# 05_UART_Interface.net
KiCad netlist of a schematic drawn in Altium Designer
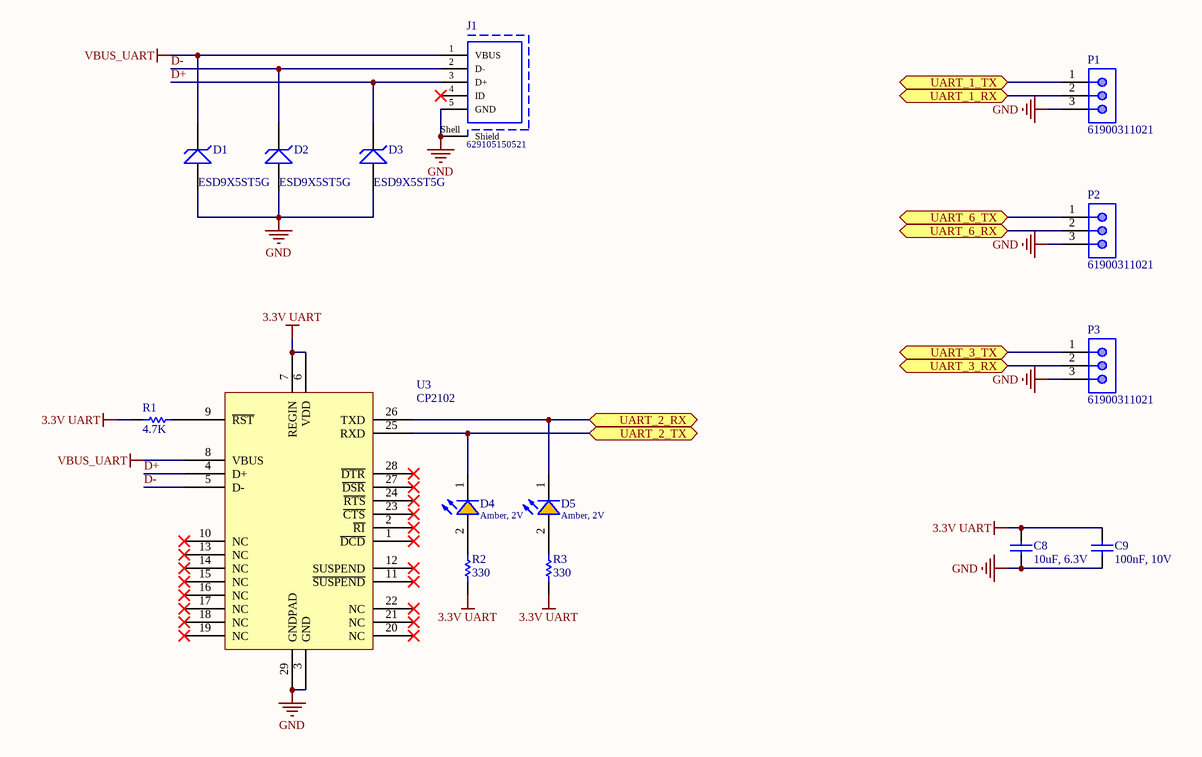
[diagram p0: 05_UART_Interface.SchDoc]

(export (version "E")
  (design (tool "Eeschema 10.0.6"))
  (components
    (comp (ref "C8")
      (value "10uF, 6.3V")
      (footprint "WCAP-CSGP_0603_H=0.8mm_Reflow")
      (description "WCAP-CSGP Multilayer Ceramic Chip Capacitor, General Purpose, size 0603, X5R, 10uF, 6.3V")
      (fields
        (field (name "MANUFACTURER PART NUMBER") "885012106006")
        (field (name "MANUFACTURER") "Wurth Elektronik")
      )
      (libsource (lib "Altium_WCAP-CSGP (rev20a)") (part "885012106006"))
    )
    (comp (ref "C9")
      (value "100nF, 10V")
      (footprint "WCAP-CSGP_0603_H=0.8mm_Reflow")
      (description "WCAP-CSGP Multilayer Ceramic Chip Capacitor, General Purpose, size 0603, X7R, 100nF, 10V")
      (fields
        (field (name "MANUFACTURER PART NUMBER") "885012206020")
        (field (name "MANUFACTURER") "Wurth Elektronik")
      )
      (libsource (lib "Altium_WCAP-CSGP (rev20a)") (part "885012206020"))
    )
    (comp (ref "D1")
      (value "ESD9X5ST5G")
      (footprint "SODFL100X40-2N")
      (fields (field (name "MANUFACTURER") "ON Semiconductor"))
      (libsource (lib "MiclsLib") (part "ESD9X5ST5G"))
    )
    (comp (ref "D2")
      (value "ESD9X5ST5G")
      (footprint "SODFL100X40-2N")
      (fields (field (name "MANUFACTURER") "ON Semiconductor"))
      (libsource (lib "MiclsLib") (part "ESD9X5ST5G"))
    )
    (comp (ref "D3")
      (value "ESD9X5ST5G")
      (footprint "SODFL100X40-2N")
      (fields (field (name "MANUFACTURER") "ON Semiconductor"))
      (libsource (lib "MiclsLib") (part "ESD9X5ST5G"))
    )
    (comp (ref "D4")
      (value "Amber, 2V")
      (footprint "WL-SMCW_0603_H=0.7mm")
      (description "WL-SMCW SMT Mono-color Chip LED Waterclear, size 0603, Amber, 2V, 140deg")
      (fields (field (name "PART NUMBER") "150060AS75000") (field (name "PUBLISHER") "Wurth Elektronik"))
      (libsource (lib "Altium_WL-SMCW (rev20a)") (part "150060AS75000"))
    )
    (comp (ref "D5")
      (value "Amber, 2V")
      (footprint "WL-SMCW_0603_H=0.7mm")
      (description "WL-SMCW SMT Mono-color Chip LED Waterclear, size 0603, Amber, 2V, 140deg")
      (fields (field (name "PART NUMBER") "150060AS75000") (field (name "PUBLISHER") "Wurth Elektronik"))
      (libsource (lib "Altium_WL-SMCW (rev20a)") (part "150060AS75000"))
    )
    (comp (ref "J1")
      (value "629105150521")
      (footprint "629105150521")
      (description "Micro USB 2.0 Type B Receptacle WR-COM, Horizontal, SMT, with Pegs, High Current at Pin 1 & Pin 5")
      (fields (field (name "PUBLISHER") "Wurth Elektronik"))
      (libsource (lib "ALTIUM-WR-COM_USB_20-rev18d") (part "629105150521"))
    )
    (comp (ref "P1")
      (value "61900311021")
      (footprint "61900311021")
      (description "WR-WTB THT Male Left Angled Bottom Locking Header, pitch 2.54mm, 3p")
      (fields (field (name "PUBLISHER") "Wurth Elektronik"))
      (libsource (lib "653008114822_Altium_WR-WTB_rev20a") (part "61900311021"))
    )
    (comp (ref "P2")
      (value "61900311021")
      (footprint "61900311021")
      (description "WR-WTB THT Male Left Angled Bottom Locking Header, pitch 2.54mm, 3p")
      (fields (field (name "PUBLISHER") "Wurth Elektronik"))
      (libsource (lib "653008114822_Altium_WR-WTB_rev20a") (part "61900311021"))
    )
    (comp (ref "P3")
      (value "61900311021")
      (footprint "61900311021")
      (description "WR-WTB THT Male Left Angled Bottom Locking Header, pitch 2.54mm, 3p")
      (fields (field (name "PUBLISHER") "Wurth Elektronik"))
      (libsource (lib "653008114822_Altium_WR-WTB_rev20a") (part "61900311021"))
    )
    (comp (ref "R1")
      (value "4.7K")
      (footprint "RES-SM-0603")
      (description "Resistor")
      (fields (field (name "Comment") "RESISTOR SMD"))
      (libsource (lib "PIF_Library") (part "RESISTOR SMD"))
    )
    (comp (ref "R2")
      (value "330")
      (footprint "RES-SM-0603")
      (description "Resistor")
      (fields (field (name "Comment") "RESISTOR SMD"))
      (libsource (lib "PIF_Library") (part "RESISTOR SMD"))
    )
    (comp (ref "R3")
      (value "330")
      (footprint "RES-SM-0603")
      (description "Resistor")
      (fields (field (name "Comment") "RESISTOR SMD"))
      (libsource (lib "PIF_Library") (part "RESISTOR SMD"))
    )
    (comp (ref "U3")
      (value "CP2102")
      (footprint "QFN50P500X500X90_HS-29N")
      (libsource (lib "MiclsLib") (part "CP2102"))
    )
  )
  (nets
    (net (code "1") (name "/D+") (class "Default")
      (node (ref "D3") (pin "1") (pinfunction "1_1") (pintype "passive"))
      (node (ref "J1") (pin "3") (pinfunction "D+_3") (pintype "passive"))
      (node (ref "U3") (pin "4") (pinfunction "D+_4") (pintype "passive"))
    )
    (net (code "2") (name "/D-") (class "Default")
      (node (ref "D2") (pin "1") (pinfunction "1_1") (pintype "passive"))
      (node (ref "J1") (pin "2") (pinfunction "D-_2") (pintype "passive"))
      (node (ref "U3") (pin "5") (pinfunction "D-_5") (pintype "passive"))
    )
    (net (code "3") (name "/UART_1_RX") (class "Default")
      (node (ref "P1") (pin "2") (pinfunction "2_2") (pintype "passive"))
    )
    (net (code "4") (name "/UART_1_TX") (class "Default")
      (node (ref "P1") (pin "1") (pinfunction "1_1") (pintype "passive"))
    )
    (net (code "5") (name "/UART_2_RX") (class "Default")
      (node (ref "D5") (pin "1") (pinfunction "K_1") (pintype "passive"))
      (node (ref "U3") (pin "26") (pinfunction "TXD_26") (pintype "passive"))
    )
    (net (code "6") (name "/UART_2_TX") (class "Default")
      (node (ref "D4") (pin "1") (pinfunction "K_1") (pintype "passive"))
      (node (ref "U3") (pin "25") (pinfunction "RXD_25") (pintype "passive"))
    )
    (net (code "7") (name "/UART_3_RX") (class "Default")
      (node (ref "P3") (pin "2") (pinfunction "2_2") (pintype "passive"))
    )
    (net (code "8") (name "/UART_3_TX") (class "Default")
      (node (ref "P3") (pin "1") (pinfunction "1_1") (pintype "passive"))
    )
    (net (code "9") (name "/UART_6_RX") (class "Default")
      (node (ref "P2") (pin "2") (pinfunction "2_2") (pintype "passive"))
    )
    (net (code "10") (name "/UART_6_TX") (class "Default")
      (node (ref "P2") (pin "1") (pinfunction "1_1") (pintype "passive"))
    )
    (net (code "11") (name "3.3V UART") (class "Default")
      (node (ref "C8") (pin "2") (pinfunction "2_2") (pintype "passive"))
      (node (ref "C9") (pin "2") (pinfunction "2_2") (pintype "passive"))
      (node (ref "R1") (pin "2") (pinfunction "2_2") (pintype "passive"))
      (node (ref "R2") (pin "2") (pinfunction "2_2") (pintype "passive"))
      (node (ref "R3") (pin "2") (pinfunction "2_2") (pintype "passive"))
      (node (ref "U3") (pin "6") (pinfunction "VDD_6") (pintype "passive"))
      (node (ref "U3") (pin "7") (pinfunction "REGIN_7") (pintype "passive"))
    )
    (net (code "12") (name "GND") (class "Default")
      (node (ref "C8") (pin "1") (pinfunction "1_1") (pintype "passive"))
      (node (ref "C9") (pin "1") (pinfunction "1_1") (pintype "passive"))
      (node (ref "D1") (pin "2") (pinfunction "2_2") (pintype "passive"))
      (node (ref "D2") (pin "2") (pinfunction "2_2") (pintype "passive"))
      (node (ref "D3") (pin "2") (pinfunction "2_2") (pintype "passive"))
      (node (ref "J1") (pin "5") (pinfunction "GND_5") (pintype "passive"))
      (node (ref "J1") (pin "Shell") (pinfunction "Shield_Shell") (pintype "passive"))
      (node (ref "P1") (pin "3") (pinfunction "3_3") (pintype "passive"))
      (node (ref "P2") (pin "3") (pinfunction "3_3") (pintype "passive"))
      (node (ref "P3") (pin "3") (pinfunction "3_3") (pintype "passive"))
      (node (ref "U3") (pin "29") (pinfunction "GNDPAD_29") (pintype "passive"))
      (node (ref "U3") (pin "3") (pinfunction "GND_3") (pintype "passive"))
    )
    (net (code "13") (name "Net-(D4-A)") (class "Default")
      (node (ref "D4") (pin "2") (pinfunction "A_2") (pintype "passive"))
      (node (ref "R2") (pin "1") (pinfunction "1_1") (pintype "passive"))
    )
    (net (code "14") (name "Net-(D5-A)") (class "Default")
      (node (ref "D5") (pin "2") (pinfunction "A_2") (pintype "passive"))
      (node (ref "R3") (pin "1") (pinfunction "1_1") (pintype "passive"))
    )
    (net (code "15") (name "Net-(U3-~{RST})") (class "Default")
      (node (ref "R1") (pin "1") (pinfunction "1_1") (pintype "passive"))
      (node (ref "U3") (pin "9") (pinfunction "~{RST}_9") (pintype "passive"))
    )
    (net (code "16") (name "VBUS_UART") (class "Default")
      (node (ref "D1") (pin "1") (pinfunction "1_1") (pintype "passive"))
      (node (ref "J1") (pin "1") (pinfunction "VBUS_1") (pintype "passive"))
      (node (ref "U3") (pin "8") (pinfunction "VBUS_8") (pintype "passive"))
    )
    (net (code "17") (name "unconnected-(J1-ID-Pad4)") (class "Default")
      (node (ref "J1") (pin "4") (pinfunction "ID_4") (pintype "passive+no_connect"))
    )
    (net (code "18") (name "unconnected-(U3-NC-Pad10)") (class "Default")
      (node (ref "U3") (pin "10") (pinfunction "NC_10") (pintype "passive+no_connect"))
    )
    (net (code "19") (name "unconnected-(U3-NC-Pad13)") (class "Default")
      (node (ref "U3") (pin "13") (pinfunction "NC_13") (pintype "passive+no_connect"))
    )
    (net (code "20") (name "unconnected-(U3-NC-Pad14)") (class "Default")
      (node (ref "U3") (pin "14") (pinfunction "NC_14") (pintype "passive+no_connect"))
    )
    (net (code "21") (name "unconnected-(U3-NC-Pad15)") (class "Default")
      (node (ref "U3") (pin "15") (pinfunction "NC_15") (pintype "passive+no_connect"))
    )
    (net (code "22") (name "unconnected-(U3-NC-Pad16)") (class "Default")
      (node (ref "U3") (pin "16") (pinfunction "NC_16") (pintype "passive+no_connect"))
    )
    (net (code "23") (name "unconnected-(U3-NC-Pad17)") (class "Default")
      (node (ref "U3") (pin "17") (pinfunction "NC_17") (pintype "passive+no_connect"))
    )
    (net (code "24") (name "unconnected-(U3-NC-Pad18)") (class "Default")
      (node (ref "U3") (pin "18") (pinfunction "NC_18") (pintype "passive+no_connect"))
    )
    (net (code "25") (name "unconnected-(U3-NC-Pad19)") (class "Default")
      (node (ref "U3") (pin "19") (pinfunction "NC_19") (pintype "passive+no_connect"))
    )
    (net (code "26") (name "unconnected-(U3-NC-Pad20)") (class "Default")
      (node (ref "U3") (pin "20") (pinfunction "NC_20") (pintype "passive+no_connect"))
    )
    (net (code "27") (name "unconnected-(U3-NC-Pad21)") (class "Default")
      (node (ref "U3") (pin "21") (pinfunction "NC_21") (pintype "passive+no_connect"))
    )
    (net (code "28") (name "unconnected-(U3-NC-Pad22)") (class "Default")
      (node (ref "U3") (pin "22") (pinfunction "NC_22") (pintype "passive+no_connect"))
    )
    (net (code "29") (name "unconnected-(U3-SUSPEND-Pad12)") (class "Default")
      (node (ref "U3") (pin "12") (pinfunction "SUSPEND_12") (pintype "passive+no_connect"))
    )
    (net (code "30") (name "unconnected-(U3-~{CTS}-Pad23)") (class "Default")
      (node (ref "U3") (pin "23") (pinfunction "~{CTS}_23") (pintype "passive+no_connect"))
    )
    (net (code "31") (name "unconnected-(U3-~{DCD}-Pad1)") (class "Default")
      (node (ref "U3") (pin "1") (pinfunction "~{DCD}_1") (pintype "passive+no_connect"))
    )
    (net (code "32") (name "unconnected-(U3-~{DSR}-Pad27)") (class "Default")
      (node (ref "U3") (pin "27") (pinfunction "~{DSR}_27") (pintype "passive+no_connect"))
    )
    (net (code "33") (name "unconnected-(U3-~{DTR}-Pad28)") (class "Default")
      (node (ref "U3") (pin "28") (pinfunction "~{DTR}_28") (pintype "passive+no_connect"))
    )
    (net (code "34") (name "unconnected-(U3-~{RI}-Pad2)") (class "Default")
      (node (ref "U3") (pin "2") (pinfunction "~{RI}_2") (pintype "passive+no_connect"))
    )
    (net (code "35") (name "unconnected-(U3-~{RTS}-Pad24)") (class "Default")
      (node (ref "U3") (pin "24") (pinfunction "~{RTS}_24") (pintype "passive+no_connect"))
    )
    (net (code "36") (name "unconnected-(U3-~{SUSPEND}-Pad11)") (class "Default")
      (node (ref "U3") (pin "11") (pinfunction "~{SUSPEND}_11") (pintype "passive+no_connect"))
    )
  )
)
